# HeaderC.net
KiCad netlist of a schematic drawn in Altium Designer
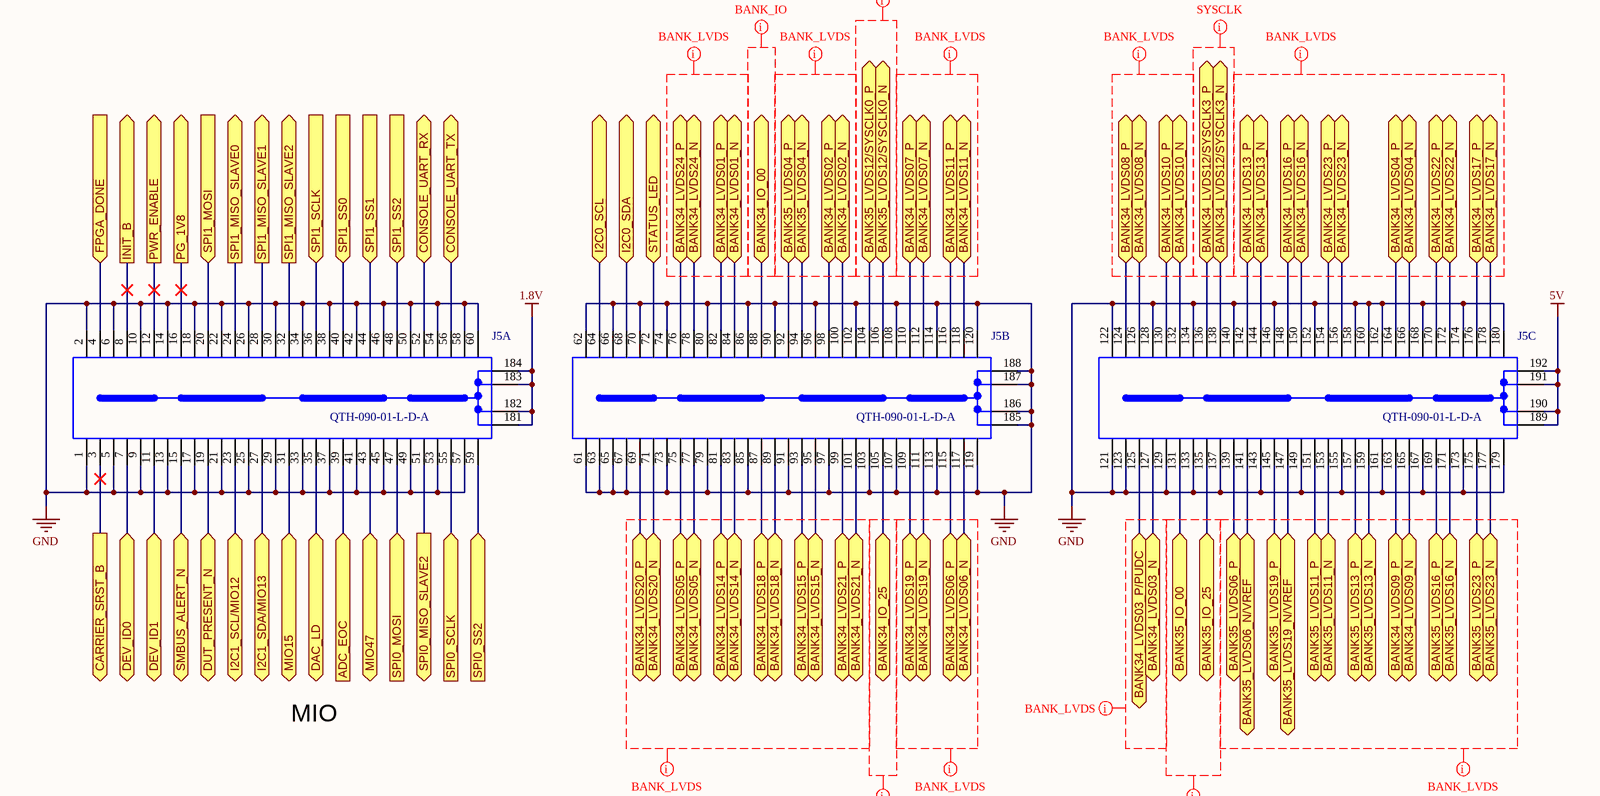
[diagram p0: HeaderC.SchDoc]

(export (version "E")
  (design (tool "Eeschema 10.0.6"))
  (components
    (comp (ref "J5")
      (value "QTH-090-01-L-D-A")
      (footprint "QTH-090-01-L-D-A")
      (description "Connector Header HS .5mm 180 pin DL AU")
      (libsource (lib "parts") (part "QTH-090-01-L-D-A"))
    )
  )
  (nets
    (net (code "1") (name "/ADC_EOC") (class "Default")
      (node (ref "J5") (pin "39") (pinfunction "39_39") (pintype "passive"))
    )
    (net (code "2") (name "/BANK34_IO_00") (class "Default")
      (node (ref "J5") (pin "88") (pinfunction "88_88") (pintype "passive"))
    )
    (net (code "3") (name "/BANK34_IO_25") (class "Default")
      (node (ref "J5") (pin "105") (pinfunction "105_105") (pintype "passive"))
    )
    (net (code "4") (name "/BANK34_LVDS01_N") (class "Default")
      (node (ref "J5") (pin "84") (pinfunction "84_84") (pintype "passive"))
    )
    (net (code "5") (name "/BANK34_LVDS01_P") (class "Default")
      (node (ref "J5") (pin "82") (pinfunction "82_82") (pintype "passive"))
    )
    (net (code "6") (name "/BANK34_LVDS02_N") (class "Default")
      (node (ref "J5") (pin "100") (pinfunction "100_100") (pintype "passive"))
    )
    (net (code "7") (name "/BANK34_LVDS02_P") (class "Default")
      (node (ref "J5") (pin "98") (pinfunction "98_98") (pintype "passive"))
    )
    (net (code "8") (name "/BANK34_LVDS03_N") (class "Default")
      (node (ref "J5") (pin "127") (pinfunction "127_127") (pintype "passive"))
    )
    (net (code "9") (name "/BANK34_LVDS03_P{slash}PUDC") (class "Default")
      (node (ref "J5") (pin "125") (pinfunction "125_125") (pintype "passive"))
    )
    (net (code "10") (name "/BANK34_LVDS04_N") (class "Default")
      (node (ref "J5") (pin "166") (pinfunction "166_166") (pintype "passive"))
    )
    (net (code "11") (name "/BANK34_LVDS04_P") (class "Default")
      (node (ref "J5") (pin "164") (pinfunction "164_164") (pintype "passive"))
    )
    (net (code "12") (name "/BANK34_LVDS05_N") (class "Default")
      (node (ref "J5") (pin "77") (pinfunction "77_77") (pintype "passive"))
    )
    (net (code "13") (name "/BANK34_LVDS05_P") (class "Default")
      (node (ref "J5") (pin "75") (pinfunction "75_75") (pintype "passive"))
    )
    (net (code "14") (name "/BANK34_LVDS06_N") (class "Default")
      (node (ref "J5") (pin "117") (pinfunction "117_117") (pintype "passive"))
    )
    (net (code "15") (name "/BANK34_LVDS06_P") (class "Default")
      (node (ref "J5") (pin "115") (pinfunction "115_115") (pintype "passive"))
    )
    (net (code "16") (name "/BANK34_LVDS07_N") (class "Default")
      (node (ref "J5") (pin "112") (pinfunction "112_112") (pintype "passive"))
    )
    (net (code "17") (name "/BANK34_LVDS07_P") (class "Default")
      (node (ref "J5") (pin "110") (pinfunction "110_110") (pintype "passive"))
    )
    (net (code "18") (name "/BANK34_LVDS08_N") (class "Default")
      (node (ref "J5") (pin "126") (pinfunction "126_126") (pintype "passive"))
    )
    (net (code "19") (name "/BANK34_LVDS08_P") (class "Default")
      (node (ref "J5") (pin "124") (pinfunction "124_124") (pintype "passive"))
    )
    (net (code "20") (name "/BANK34_LVDS09_N") (class "Default")
      (node (ref "J5") (pin "165") (pinfunction "165_165") (pintype "passive"))
    )
    (net (code "21") (name "/BANK34_LVDS09_P") (class "Default")
      (node (ref "J5") (pin "163") (pinfunction "163_163") (pintype "passive"))
    )
    (net (code "22") (name "/BANK34_LVDS10_N") (class "Default")
      (node (ref "J5") (pin "132") (pinfunction "132_132") (pintype "passive"))
    )
    (net (code "23") (name "/BANK34_LVDS10_P") (class "Default")
      (node (ref "J5") (pin "130") (pinfunction "130_130") (pintype "passive"))
    )
    (net (code "24") (name "/BANK34_LVDS11_N") (class "Default")
      (node (ref "J5") (pin "118") (pinfunction "118_118") (pintype "passive"))
    )
    (net (code "25") (name "/BANK34_LVDS11_P") (class "Default")
      (node (ref "J5") (pin "116") (pinfunction "116_116") (pintype "passive"))
    )
    (net (code "26") (name "/BANK34_LVDS12{slash}SYSCLK3_N") (class "Default")
      (node (ref "J5") (pin "138") (pinfunction "138_138") (pintype "passive"))
    )
    (net (code "27") (name "/BANK34_LVDS12{slash}SYSCLK3_P") (class "Default")
      (node (ref "J5") (pin "136") (pinfunction "136_136") (pintype "passive"))
    )
    (net (code "28") (name "/BANK34_LVDS13_N") (class "Default")
      (node (ref "J5") (pin "144") (pinfunction "144_144") (pintype "passive"))
    )
    (net (code "29") (name "/BANK34_LVDS13_P") (class "Default")
      (node (ref "J5") (pin "142") (pinfunction "142_142") (pintype "passive"))
    )
    (net (code "30") (name "/BANK34_LVDS14_N") (class "Default")
      (node (ref "J5") (pin "83") (pinfunction "83_83") (pintype "passive"))
    )
    (net (code "31") (name "/BANK34_LVDS14_P") (class "Default")
      (node (ref "J5") (pin "81") (pinfunction "81_81") (pintype "passive"))
    )
    (net (code "32") (name "/BANK34_LVDS15_N") (class "Default")
      (node (ref "J5") (pin "95") (pinfunction "95_95") (pintype "passive"))
    )
    (net (code "33") (name "/BANK34_LVDS15_P") (class "Default")
      (node (ref "J5") (pin "93") (pinfunction "93_93") (pintype "passive"))
    )
    (net (code "34") (name "/BANK34_LVDS16_N") (class "Default")
      (node (ref "J5") (pin "150") (pinfunction "150_150") (pintype "passive"))
    )
    (net (code "35") (name "/BANK34_LVDS16_P") (class "Default")
      (node (ref "J5") (pin "148") (pinfunction "148_148") (pintype "passive"))
    )
    (net (code "36") (name "/BANK34_LVDS17_N") (class "Default")
      (node (ref "J5") (pin "178") (pinfunction "178_178") (pintype "passive"))
    )
    (net (code "37") (name "/BANK34_LVDS17_P") (class "Default")
      (node (ref "J5") (pin "176") (pinfunction "176_176") (pintype "passive"))
    )
    (net (code "38") (name "/BANK34_LVDS18_N") (class "Default")
      (node (ref "J5") (pin "89") (pinfunction "89_89") (pintype "passive"))
    )
    (net (code "39") (name "/BANK34_LVDS18_P") (class "Default")
      (node (ref "J5") (pin "87") (pinfunction "87_87") (pintype "passive"))
    )
    (net (code "40") (name "/BANK34_LVDS19_N") (class "Default")
      (node (ref "J5") (pin "111") (pinfunction "111_111") (pintype "passive"))
    )
    (net (code "41") (name "/BANK34_LVDS19_P") (class "Default")
      (node (ref "J5") (pin "109") (pinfunction "109_109") (pintype "passive"))
    )
    (net (code "42") (name "/BANK34_LVDS20_N") (class "Default")
      (node (ref "J5") (pin "71") (pinfunction "71_71") (pintype "passive"))
    )
    (net (code "43") (name "/BANK34_LVDS20_P") (class "Default")
      (node (ref "J5") (pin "69") (pinfunction "69_69") (pintype "passive"))
    )
    (net (code "44") (name "/BANK34_LVDS21_N") (class "Default")
      (node (ref "J5") (pin "101") (pinfunction "101_101") (pintype "passive"))
    )
    (net (code "45") (name "/BANK34_LVDS21_P") (class "Default")
      (node (ref "J5") (pin "99") (pinfunction "99_99") (pintype "passive"))
    )
    (net (code "46") (name "/BANK34_LVDS22_N") (class "Default")
      (node (ref "J5") (pin "172") (pinfunction "172_172") (pintype "passive"))
    )
    (net (code "47") (name "/BANK34_LVDS22_P") (class "Default")
      (node (ref "J5") (pin "170") (pinfunction "170_170") (pintype "passive"))
    )
    (net (code "48") (name "/BANK34_LVDS23_N") (class "Default")
      (node (ref "J5") (pin "156") (pinfunction "156_156") (pintype "passive"))
    )
    (net (code "49") (name "/BANK34_LVDS23_P") (class "Default")
      (node (ref "J5") (pin "154") (pinfunction "154_154") (pintype "passive"))
    )
    (net (code "50") (name "/BANK34_LVDS24_N") (class "Default")
      (node (ref "J5") (pin "78") (pinfunction "78_78") (pintype "passive"))
    )
    (net (code "51") (name "/BANK34_LVDS24_P") (class "Default")
      (node (ref "J5") (pin "76") (pinfunction "76_76") (pintype "passive"))
    )
    (net (code "52") (name "/BANK35_IO_00") (class "Default")
      (node (ref "J5") (pin "131") (pinfunction "131_131") (pintype "passive"))
    )
    (net (code "53") (name "/BANK35_IO_25") (class "Default")
      (node (ref "J5") (pin "135") (pinfunction "135_135") (pintype "passive"))
    )
    (net (code "54") (name "/BANK35_LVDS04_N") (class "Default")
      (node (ref "J5") (pin "94") (pinfunction "94_94") (pintype "passive"))
    )
    (net (code "55") (name "/BANK35_LVDS04_P") (class "Default")
      (node (ref "J5") (pin "92") (pinfunction "92_92") (pintype "passive"))
    )
    (net (code "56") (name "/BANK35_LVDS06_N{slash}VREF") (class "Default")
      (node (ref "J5") (pin "141") (pinfunction "141_141") (pintype "passive"))
    )
    (net (code "57") (name "/BANK35_LVDS06_P") (class "Default")
      (node (ref "J5") (pin "139") (pinfunction "139_139") (pintype "passive"))
    )
    (net (code "58") (name "/BANK35_LVDS11_N") (class "Default")
      (node (ref "J5") (pin "153") (pinfunction "153_153") (pintype "passive"))
    )
    (net (code "59") (name "/BANK35_LVDS11_P") (class "Default")
      (node (ref "J5") (pin "151") (pinfunction "151_151") (pintype "passive"))
    )
    (net (code "60") (name "/BANK35_LVDS12{slash}SYSCLK0_N") (class "Default")
      (node (ref "J5") (pin "106") (pinfunction "106_106") (pintype "passive"))
    )
    (net (code "61") (name "/BANK35_LVDS12{slash}SYSCLK0_P") (class "Default")
      (node (ref "J5") (pin "104") (pinfunction "104_104") (pintype "passive"))
    )
    (net (code "62") (name "/BANK35_LVDS13_N") (class "Default")
      (node (ref "J5") (pin "159") (pinfunction "159_159") (pintype "passive"))
    )
    (net (code "63") (name "/BANK35_LVDS13_P") (class "Default")
      (node (ref "J5") (pin "157") (pinfunction "157_157") (pintype "passive"))
    )
    (net (code "64") (name "/BANK35_LVDS16_N") (class "Default")
      (node (ref "J5") (pin "171") (pinfunction "171_171") (pintype "passive"))
    )
    (net (code "65") (name "/BANK35_LVDS16_P") (class "Default")
      (node (ref "J5") (pin "169") (pinfunction "169_169") (pintype "passive"))
    )
    (net (code "66") (name "/BANK35_LVDS19_N{slash}VREF") (class "Default")
      (node (ref "J5") (pin "147") (pinfunction "147_147") (pintype "passive"))
    )
    (net (code "67") (name "/BANK35_LVDS19_P") (class "Default")
      (node (ref "J5") (pin "145") (pinfunction "145_145") (pintype "passive"))
    )
    (net (code "68") (name "/BANK35_LVDS23_N") (class "Default")
      (node (ref "J5") (pin "177") (pinfunction "177_177") (pintype "passive"))
    )
    (net (code "69") (name "/BANK35_LVDS23_P") (class "Default")
      (node (ref "J5") (pin "175") (pinfunction "175_175") (pintype "passive"))
    )
    (net (code "70") (name "/CARRIER_SRST_B") (class "Default")
      (node (ref "J5") (pin "3") (pinfunction "3_3") (pintype "passive"))
    )
    (net (code "71") (name "/CONSOLE_UART_RX") (class "Default")
      (node (ref "J5") (pin "52") (pinfunction "52_52") (pintype "passive"))
    )
    (net (code "72") (name "/CONSOLE_UART_TX") (class "Default")
      (node (ref "J5") (pin "56") (pinfunction "56_56") (pintype "passive"))
    )
    (net (code "73") (name "/DAC_LD") (class "Default")
      (node (ref "J5") (pin "35") (pinfunction "35_35") (pintype "passive"))
    )
    (net (code "74") (name "/DEV_ID0") (class "Default")
      (node (ref "J5") (pin "7") (pinfunction "7_7") (pintype "passive"))
    )
    (net (code "75") (name "/DEV_ID1") (class "Default")
      (node (ref "J5") (pin "11") (pinfunction "11_11") (pintype "passive"))
    )
    (net (code "76") (name "/DUT_PRESENT_N") (class "Default")
      (node (ref "J5") (pin "19") (pinfunction "19_19") (pintype "passive"))
    )
    (net (code "77") (name "/FPGA_DONE") (class "Default")
      (node (ref "J5") (pin "4") (pinfunction "4_4") (pintype "passive"))
    )
    (net (code "78") (name "/I2C0_SCL") (class "Default")
      (node (ref "J5") (pin "64") (pinfunction "64_64") (pintype "passive"))
    )
    (net (code "79") (name "/I2C0_SDA") (class "Default")
      (node (ref "J5") (pin "68") (pinfunction "68_68") (pintype "passive"))
    )
    (net (code "80") (name "/I2C1_SCL{slash}MIO12") (class "Default")
      (node (ref "J5") (pin "23") (pinfunction "23_23") (pintype "passive"))
    )
    (net (code "81") (name "/I2C1_SDA{slash}MIO13") (class "Default")
      (node (ref "J5") (pin "27") (pinfunction "27_27") (pintype "passive"))
    )
    (net (code "82") (name "/INIT_B") (class "Default")
      (node (ref "J5") (pin "8") (pinfunction "8_8") (pintype "passive"))
    )
    (net (code "83") (name "/MIO15") (class "Default")
      (node (ref "J5") (pin "31") (pinfunction "31_31") (pintype "passive"))
    )
    (net (code "84") (name "/MIO47") (class "Default")
      (node (ref "J5") (pin "43") (pinfunction "43_43") (pintype "passive"))
    )
    (net (code "85") (name "/PG_1V8") (class "Default")
      (node (ref "J5") (pin "16") (pinfunction "16_16") (pintype "passive"))
    )
    (net (code "86") (name "/PWR_ENABLE") (class "Default")
      (node (ref "J5") (pin "12") (pinfunction "12_12") (pintype "passive"))
    )
    (net (code "87") (name "/SMBUS_ALERT_N") (class "Default")
      (node (ref "J5") (pin "15") (pinfunction "15_15") (pintype "passive"))
    )
    (net (code "88") (name "/SPI0_MISO_SLAVE2") (class "Default")
      (node (ref "J5") (pin "51") (pinfunction "51_51") (pintype "passive"))
    )
    (net (code "89") (name "/SPI0_MOSI") (class "Default")
      (node (ref "J5") (pin "47") (pinfunction "47_47") (pintype "passive"))
    )
    (net (code "90") (name "/SPI0_SCLK") (class "Default")
      (node (ref "J5") (pin "55") (pinfunction "55_55") (pintype "passive"))
    )
    (net (code "91") (name "/SPI0_SS2") (class "Default")
      (node (ref "J5") (pin "59") (pinfunction "59_59") (pintype "passive"))
    )
    (net (code "92") (name "/SPI1_MISO_SLAVE0") (class "Default")
      (node (ref "J5") (pin "24") (pinfunction "24_24") (pintype "passive"))
    )
    (net (code "93") (name "/SPI1_MISO_SLAVE1") (class "Default")
      (node (ref "J5") (pin "28") (pinfunction "28_28") (pintype "passive"))
    )
    (net (code "94") (name "/SPI1_MISO_SLAVE2") (class "Default")
      (node (ref "J5") (pin "32") (pinfunction "32_32") (pintype "passive"))
    )
    (net (code "95") (name "/SPI1_MOSI") (class "Default")
      (node (ref "J5") (pin "20") (pinfunction "20_20") (pintype "passive"))
    )
    (net (code "96") (name "/SPI1_SCLK") (class "Default")
      (node (ref "J5") (pin "36") (pinfunction "36_36") (pintype "passive"))
    )
    (net (code "97") (name "/SPI1_SS0") (class "Default")
      (node (ref "J5") (pin "40") (pinfunction "40_40") (pintype "passive"))
    )
    (net (code "98") (name "/SPI1_SS1") (class "Default")
      (node (ref "J5") (pin "44") (pinfunction "44_44") (pintype "passive"))
    )
    (net (code "99") (name "/SPI1_SS2") (class "Default")
      (node (ref "J5") (pin "48") (pinfunction "48_48") (pintype "passive"))
    )
    (net (code "100") (name "/STATUS_LED") (class "Default")
      (node (ref "J5") (pin "72") (pinfunction "72_72") (pintype "passive"))
    )
    (net (code "101") (name "1.8V") (class "Default")
      (node (ref "J5") (pin "181") (pinfunction "181_181") (pintype "passive"))
      (node (ref "J5") (pin "182") (pinfunction "182_182") (pintype "passive"))
      (node (ref "J5") (pin "183") (pinfunction "183_183") (pintype "passive"))
      (node (ref "J5") (pin "184") (pinfunction "184_184") (pintype "passive"))
    )
    (net (code "102") (name "5V") (class "Default")
      (node (ref "J5") (pin "189") (pinfunction "189_189") (pintype "passive"))
      (node (ref "J5") (pin "190") (pinfunction "190_190") (pintype "passive"))
      (node (ref "J5") (pin "191") (pinfunction "191_191") (pintype "passive"))
      (node (ref "J5") (pin "192") (pinfunction "192_192") (pintype "passive"))
    )
    (net (code "103") (name "GND") (class "Default")
      (node (ref "J5") (pin "1") (pinfunction "1_1") (pintype "passive"))
      (node (ref "J5") (pin "10") (pinfunction "10_10") (pintype "passive"))
      (node (ref "J5") (pin "102") (pinfunction "102_102") (pintype "passive"))
      (node (ref "J5") (pin "103") (pinfunction "103_103") (pintype "passive"))
      (node (ref "J5") (pin "107") (pinfunction "107_107") (pintype "passive"))
      (node (ref "J5") (pin "108") (pinfunction "108_108") (pintype "passive"))
      (node (ref "J5") (pin "113") (pinfunction "113_113") (pintype "passive"))
      (node (ref "J5") (pin "114") (pinfunction "114_114") (pintype "passive"))
      (node (ref "J5") (pin "119") (pinfunction "119_119") (pintype "passive"))
      (node (ref "J5") (pin "120") (pinfunction "120_120") (pintype "passive"))
      (node (ref "J5") (pin "121") (pinfunction "121_121") (pintype "passive"))
      (node (ref "J5") (pin "122") (pinfunction "122_122") (pintype "passive"))
      (node (ref "J5") (pin "123") (pinfunction "123_123") (pintype "passive"))
      (node (ref "J5") (pin "128") (pinfunction "128_128") (pintype "passive"))
      (node (ref "J5") (pin "129") (pinfunction "129_129") (pintype "passive"))
      (node (ref "J5") (pin "13") (pinfunction "13_13") (pintype "passive"))
      (node (ref "J5") (pin "133") (pinfunction "133_133") (pintype "passive"))
      (node (ref "J5") (pin "134") (pinfunction "134_134") (pintype "passive"))
      (node (ref "J5") (pin "137") (pinfunction "137_137") (pintype "passive"))
      (node (ref "J5") (pin "14") (pinfunction "14_14") (pintype "passive"))
      (node (ref "J5") (pin "140") (pinfunction "140_140") (pintype "passive"))
      (node (ref "J5") (pin "143") (pinfunction "143_143") (pintype "passive"))
      (node (ref "J5") (pin "146") (pinfunction "146_146") (pintype "passive"))
      (node (ref "J5") (pin "149") (pinfunction "149_149") (pintype "passive"))
      (node (ref "J5") (pin "152") (pinfunction "152_152") (pintype "passive"))
      (node (ref "J5") (pin "155") (pinfunction "155_155") (pintype "passive"))
      (node (ref "J5") (pin "158") (pinfunction "158_158") (pintype "passive"))
      (node (ref "J5") (pin "160") (pinfunction "160_160") (pintype "passive"))
      (node (ref "J5") (pin "161") (pinfunction "161_161") (pintype "passive"))
      (node (ref "J5") (pin "162") (pinfunction "162_162") (pintype "passive"))
      (node (ref "J5") (pin "167") (pinfunction "167_167") (pintype "passive"))
      (node (ref "J5") (pin "168") (pinfunction "168_168") (pintype "passive"))
      (node (ref "J5") (pin "17") (pinfunction "17_17") (pintype "passive"))
      (node (ref "J5") (pin "173") (pinfunction "173_173") (pintype "passive"))
      (node (ref "J5") (pin "174") (pinfunction "174_174") (pintype "passive"))
      (node (ref "J5") (pin "179") (pinfunction "179_179") (pintype "passive"))
      (node (ref "J5") (pin "18") (pinfunction "18_18") (pintype "passive"))
      (node (ref "J5") (pin "180") (pinfunction "180_180") (pintype "passive"))
      (node (ref "J5") (pin "185") (pinfunction "185_185") (pintype "passive"))
      (node (ref "J5") (pin "186") (pinfunction "186_186") (pintype "passive"))
      (node (ref "J5") (pin "187") (pinfunction "187_187") (pintype "passive"))
      (node (ref "J5") (pin "188") (pinfunction "188_188") (pintype "passive"))
      (node (ref "J5") (pin "2") (pinfunction "2_2") (pintype "passive"))
      (node (ref "J5") (pin "21") (pinfunction "21_21") (pintype "passive"))
      (node (ref "J5") (pin "22") (pinfunction "22_22") (pintype "passive"))
      (node (ref "J5") (pin "25") (pinfunction "25_25") (pintype "passive"))
      (node (ref "J5") (pin "26") (pinfunction "26_26") (pintype "passive"))
      (node (ref "J5") (pin "29") (pinfunction "29_29") (pintype "passive"))
      (node (ref "J5") (pin "30") (pinfunction "30_30") (pintype "passive"))
      (node (ref "J5") (pin "33") (pinfunction "33_33") (pintype "passive"))
      (node (ref "J5") (pin "34") (pinfunction "34_34") (pintype "passive"))
      (node (ref "J5") (pin "37") (pinfunction "37_37") (pintype "passive"))
      (node (ref "J5") (pin "38") (pinfunction "38_38") (pintype "passive"))
      (node (ref "J5") (pin "41") (pinfunction "41_41") (pintype "passive"))
      (node (ref "J5") (pin "42") (pinfunction "42_42") (pintype "passive"))
      (node (ref "J5") (pin "45") (pinfunction "45_45") (pintype "passive"))
      (node (ref "J5") (pin "46") (pinfunction "46_46") (pintype "passive"))
      (node (ref "J5") (pin "49") (pinfunction "49_49") (pintype "passive"))
      (node (ref "J5") (pin "5") (pinfunction "5_5") (pintype "passive"))
      (node (ref "J5") (pin "50") (pinfunction "50_50") (pintype "passive"))
      (node (ref "J5") (pin "53") (pinfunction "53_53") (pintype "passive"))
      (node (ref "J5") (pin "54") (pinfunction "54_54") (pintype "passive"))
      (node (ref "J5") (pin "57") (pinfunction "57_57") (pintype "passive"))
      (node (ref "J5") (pin "58") (pinfunction "58_58") (pintype "passive"))
      (node (ref "J5") (pin "6") (pinfunction "6_6") (pintype "passive"))
      (node (ref "J5") (pin "60") (pinfunction "60_60") (pintype "passive"))
      (node (ref "J5") (pin "61") (pinfunction "61_61") (pintype "passive"))
      (node (ref "J5") (pin "62") (pinfunction "62_62") (pintype "passive"))
      (node (ref "J5") (pin "63") (pinfunction "63_63") (pintype "passive"))
      (node (ref "J5") (pin "65") (pinfunction "65_65") (pintype "passive"))
      (node (ref "J5") (pin "66") (pinfunction "66_66") (pintype "passive"))
      (node (ref "J5") (pin "67") (pinfunction "67_67") (pintype "passive"))
      (node (ref "J5") (pin "70") (pinfunction "70_70") (pintype "passive"))
      (node (ref "J5") (pin "73") (pinfunction "73_73") (pintype "passive"))
      (node (ref "J5") (pin "74") (pinfunction "74_74") (pintype "passive"))
      (node (ref "J5") (pin "79") (pinfunction "79_79") (pintype "passive"))
      (node (ref "J5") (pin "80") (pinfunction "80_80") (pintype "passive"))
      (node (ref "J5") (pin "85") (pinfunction "85_85") (pintype "passive"))
      (node (ref "J5") (pin "86") (pinfunction "86_86") (pintype "passive"))
      (node (ref "J5") (pin "9") (pinfunction "9_9") (pintype "passive"))
      (node (ref "J5") (pin "90") (pinfunction "90_90") (pintype "passive"))
      (node (ref "J5") (pin "91") (pinfunction "91_91") (pintype "passive"))
      (node (ref "J5") (pin "96") (pinfunction "96_96") (pintype "passive"))
      (node (ref "J5") (pin "97") (pinfunction "97_97") (pintype "passive"))
    )
  )
)
